# SiPM_ASSY.net
KiCad netlist of a schematic drawn in Altium Designer
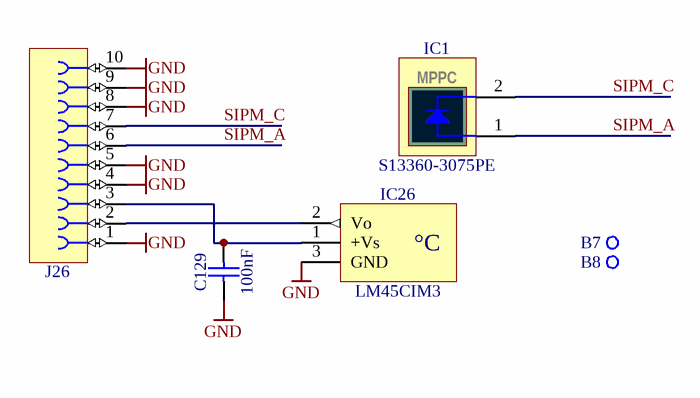
[diagram p0: SiPM_ASSY.SchDoc]

(export (version "E")
  (design (tool "Eeschema 10.0.6"))
  (components
    (comp (ref "B7")
      (value "Plated Hole")
      (footprint "MTG270_500")
      (description "Single Terminal Socket")
      (fields (field (name "PART NUMBER") "PLATED_HOLE2.7_PAD5.0") (field (name "AUTHOR") "CERN DEM JMW"))
      (libsource (lib "Eletro-mechanical") (part "Single Terminal Socket"))
    )
    (comp (ref "B8")
      (value "Plated Hole")
      (footprint "MTG270_500")
      (description "Single Terminal Socket")
      (fields (field (name "PART NUMBER") "PLATED_HOLE2.7_PAD5.0") (field (name "AUTHOR") "CERN DEM JMW"))
      (libsource (lib "Eletro-mechanical") (part "Single Terminal Socket"))
    )
    (comp (ref "C129")
      (value "100nF")
      (footprint "CAPC1005X55N")
      (description "Non-polarised capacitor")
      (fields
        (field (name "PART NUMBER") "CC0402_100NF_16V_10%_X7R")
        (field (name "VOLTAGE") "16V")
        (field (name "AUTHOR") "CERN DEM JLC")
      )
      (libsource (lib "Capacitors") (part "Capacitor - non polarized"))
    )
    (comp (ref "IC1")
      (value "S13360-3075PE")
      (footprint "HAMAMATSU_S13360-3075PE")
      (description "MPPC (Multi-Pixel Photon Counter)")
      (fields (field (name "MANUFACTURER") "HAMAMATSU") (field (name "AUTHOR") "GK"))
      (libsource (lib "Sensors") (part "SENS_S13360-3075PE"))
    )
    (comp (ref "IC26")
      (value "LM45CIM3")
      (footprint "SOT95P251X112-3N")
      (description "-20° to +100°C ±3°C Precision Centigrade Temperature Sensors")
      (fields (field (name "MANUFACTURER") "NATIONAL SEMICONDUCTOR") (field (name "AUTHOR") "CERN DEM JLC"))
      (libsource (lib "ICs And Semiconductors") (part "LM45"))
    )
    (comp (ref "J26")
      (value "FFC/FPC")
      (footprint "MOLEX_52745-1097")
      (description "Connector 10 Female")
      (fields
        (field (name "PART NUMBER") "MOLEX_52745-1097")
        (field (name "MANUFACTURER") "MOLEX")
        (field (name "AUTHOR") "CERN DEM JLC")
      )
      (libsource (lib "Connectors") (part "Connector 10 Female"))
    )
  )
  (nets
    (net (code "1") (name "/SIPM_A") (class "Default")
      (node (ref "IC1") (pin "1") (pinfunction "A_1") (pintype "passive"))
      (node (ref "J26") (pin "6") (pinfunction "6_6") (pintype "bidirectional"))
    )
    (net (code "2") (name "/SIPM_C") (class "Default")
      (node (ref "IC1") (pin "2") (pinfunction "C_2") (pintype "passive"))
      (node (ref "J26") (pin "7") (pinfunction "7_7") (pintype "bidirectional"))
    )
    (net (code "3") (name "GND") (class "Default")
      (node (ref "C129") (pin "1") (pinfunction "1_1") (pintype "passive"))
      (node (ref "IC26") (pin "3") (pinfunction "GND_3") (pintype "power_in"))
      (node (ref "J26") (pin "1") (pinfunction "1_1") (pintype "bidirectional"))
      (node (ref "J26") (pin "10") (pinfunction "10_10") (pintype "bidirectional"))
      (node (ref "J26") (pin "4") (pinfunction "4_4") (pintype "bidirectional"))
      (node (ref "J26") (pin "5") (pinfunction "5_5") (pintype "bidirectional"))
      (node (ref "J26") (pin "8") (pinfunction "8_8") (pintype "bidirectional"))
      (node (ref "J26") (pin "9") (pinfunction "9_9") (pintype "bidirectional"))
    )
    (net (code "4") (name "Net-(IC26-+Vs)") (class "Default")
      (node (ref "C129") (pin "2") (pinfunction "2_2") (pintype "passive"))
      (node (ref "IC26") (pin "1") (pinfunction "+Vs_1") (pintype "power_in"))
      (node (ref "J26") (pin "3") (pinfunction "3_3") (pintype "bidirectional"))
    )
    (net (code "5") (name "Net-(IC26-Vo)") (class "Default")
      (node (ref "IC26") (pin "2") (pinfunction "Vo_2") (pintype "output"))
      (node (ref "J26") (pin "2") (pinfunction "2_2") (pintype "bidirectional"))
    )
    (net (code "6") (name "unconnected-(B7-Pad1)") (class "Default")
      (node (ref "B7") (pin "1") (pinfunction "1_1") (pintype "bidirectional"))
    )
    (net (code "7") (name "unconnected-(B8-Pad1)") (class "Default")
      (node (ref "B8") (pin "1") (pinfunction "1_1") (pintype "bidirectional"))
    )
  )
)
